# belt_output.net
KiCad netlist of a schematic drawn in Altium Designer
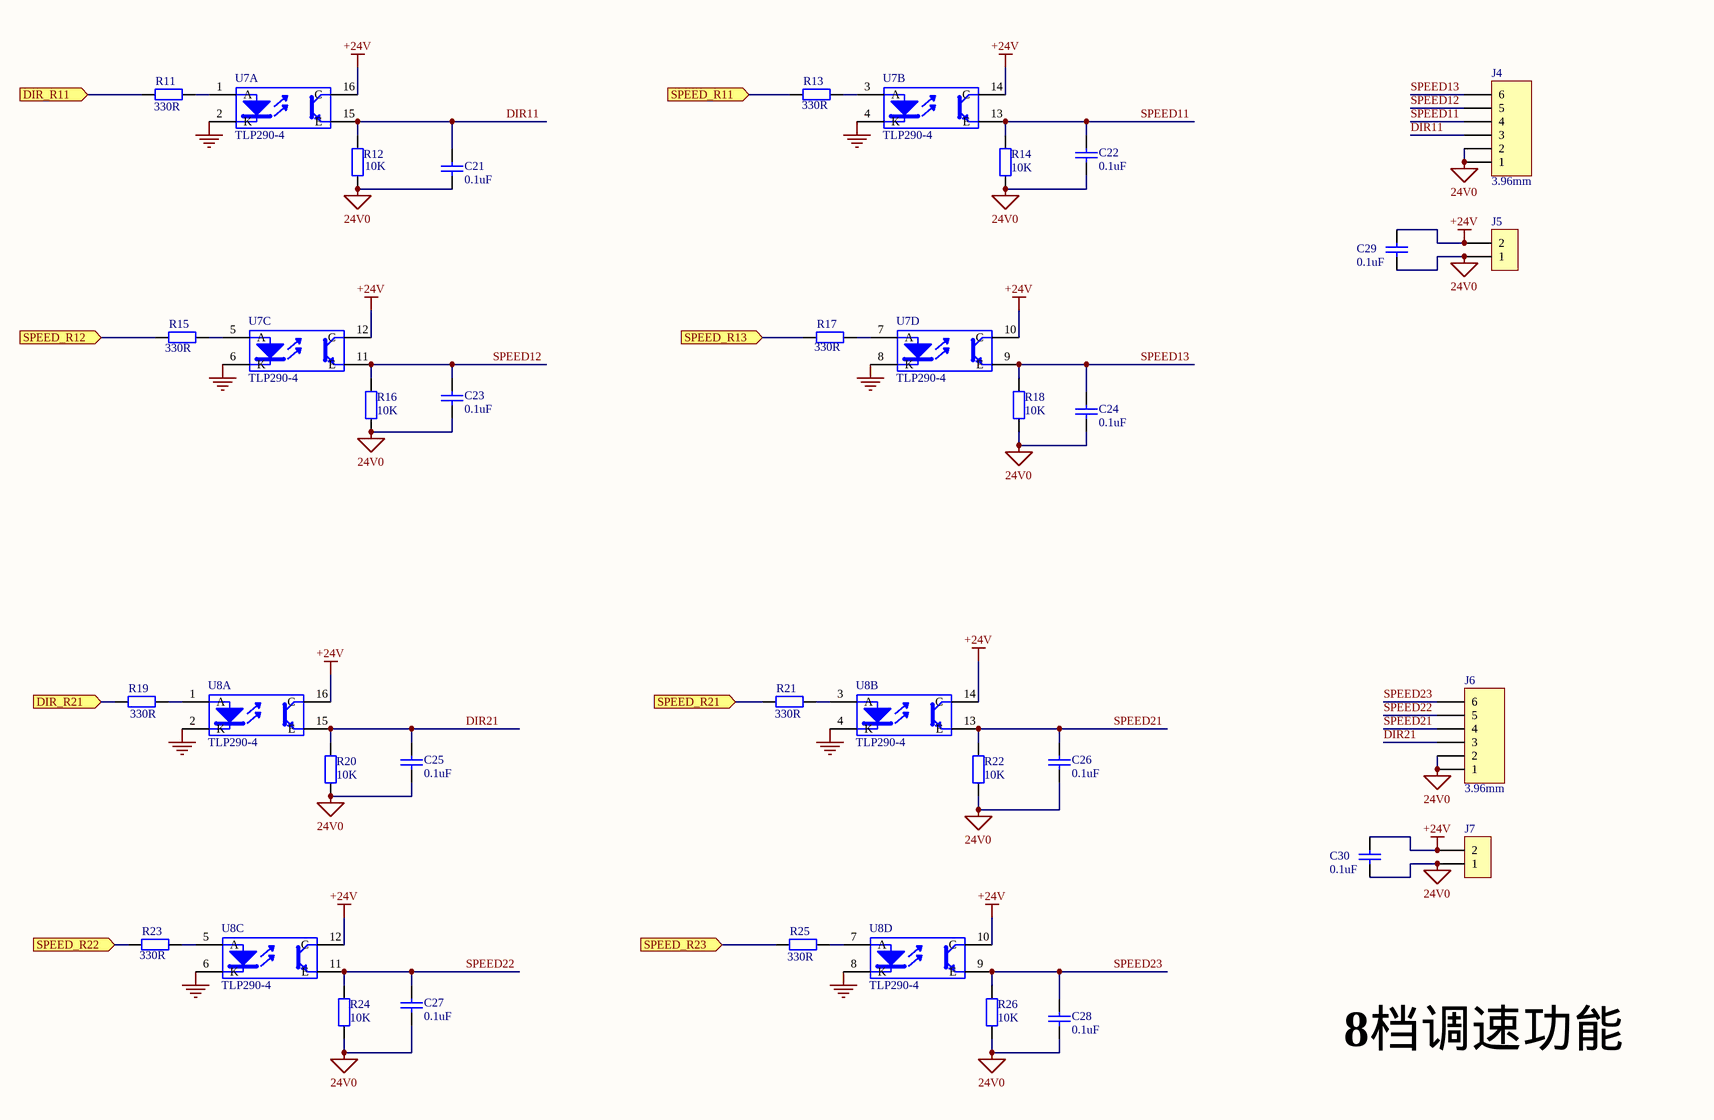
[diagram p0: belt_output.SchDoc]

(export (version "E")
  (design (tool "Eeschema 10.0.6"))
  (components
    (comp (ref "C21")
      (value "0.1uF")
      (footprint "0805_CAP")
      (description "Capacitor")
      (fields (field (name "PUBLISHER") "Altium Limited"))
      (libsource (lib "Miscellaneous Devices") (part "Cap"))
    )
    (comp (ref "C22")
      (value "0.1uF")
      (footprint "0805_CAP")
      (description "Capacitor")
      (fields (field (name "PUBLISHER") "Altium Limited"))
      (libsource (lib "Miscellaneous Devices") (part "Cap"))
    )
    (comp (ref "C23")
      (value "0.1uF")
      (footprint "0805_CAP")
      (description "Capacitor")
      (fields (field (name "PUBLISHER") "Altium Limited"))
      (libsource (lib "Miscellaneous Devices") (part "Cap"))
    )
    (comp (ref "C24")
      (value "0.1uF")
      (footprint "0805_CAP")
      (description "Capacitor")
      (fields (field (name "PUBLISHER") "Altium Limited"))
      (libsource (lib "Miscellaneous Devices") (part "Cap"))
    )
    (comp (ref "C25")
      (value "0.1uF")
      (footprint "0805_CAP")
      (description "Capacitor")
      (fields (field (name "PUBLISHER") "Altium Limited"))
      (libsource (lib "Miscellaneous Devices") (part "Cap"))
    )
    (comp (ref "C26")
      (value "0.1uF")
      (footprint "0805_CAP")
      (description "Capacitor")
      (fields (field (name "PUBLISHER") "Altium Limited"))
      (libsource (lib "Miscellaneous Devices") (part "Cap"))
    )
    (comp (ref "C27")
      (value "0.1uF")
      (footprint "0805_CAP")
      (description "Capacitor")
      (fields (field (name "PUBLISHER") "Altium Limited"))
      (libsource (lib "Miscellaneous Devices") (part "Cap"))
    )
    (comp (ref "C28")
      (value "0.1uF")
      (footprint "0805_CAP")
      (description "Capacitor")
      (fields (field (name "PUBLISHER") "Altium Limited"))
      (libsource (lib "Miscellaneous Devices") (part "Cap"))
    )
    (comp (ref "C29")
      (value "0.1uF")
      (footprint "0805_CAP")
      (description "Capacitor")
      (fields (field (name "PUBLISHER") "Altium Limited"))
      (libsource (lib "Miscellaneous Devices") (part "Cap"))
    )
    (comp (ref "C30")
      (value "0.1uF")
      (footprint "0805_CAP")
      (description "Capacitor")
      (fields (field (name "PUBLISHER") "Altium Limited"))
      (libsource (lib "Miscellaneous Devices") (part "Cap"))
    )
    (comp (ref "J4")
      (value "3.96mm")
      (footprint "VH3.96_6P")
      (description "Header, 6-Pin, Right Angle")
      (fields (field (name "PUBLISHER") "Altium Limited"))
      (libsource (lib "Miscellaneous Connectors") (part "Header 6H"))
    )
    (comp (ref "J5")
      (value "HEADER1X2")
      (footprint "VH3.96_2P")
      (libsource (lib "myIntegrated_Library1") (part "HEADER1X2"))
    )
    (comp (ref "J6")
      (value "3.96mm")
      (footprint "VH3.96_6P")
      (description "Header, 6-Pin")
      (fields (field (name "PUBLISHER") "Altium Limited"))
      (libsource (lib "Miscellaneous Connectors") (part "Header 6"))
    )
    (comp (ref "J7")
      (value "HEADER1X2")
      (footprint "VH3.96_2P")
      (libsource (lib "myIntegrated_Library1") (part "HEADER1X2"))
    )
    (comp (ref "R11")
      (value "330R")
      (footprint "0805_RES")
      (description "Resistor")
      (fields (field (name "PUBLISHER") "Altium Limited"))
      (libsource (lib "Miscellaneous Devices") (part "Res2"))
    )
    (comp (ref "R12")
      (value "10K")
      (footprint "0805_RES")
      (description "Resistor")
      (fields (field (name "PUBLISHER") "Altium Limited"))
      (libsource (lib "") (part "Res2_1"))
    )
    (comp (ref "R13")
      (value "330R")
      (footprint "0805_RES")
      (description "Resistor")
      (fields (field (name "PUBLISHER") "Altium Limited"))
      (libsource (lib "Miscellaneous Devices") (part "Res2"))
    )
    (comp (ref "R14")
      (value "10K")
      (footprint "0805_RES")
      (description "Resistor")
      (fields (field (name "PUBLISHER") "Altium Limited"))
      (libsource (lib "") (part "Res2_1"))
    )
    (comp (ref "R15")
      (value "330R")
      (footprint "0805_RES")
      (description "Resistor")
      (fields (field (name "PUBLISHER") "Altium Limited"))
      (libsource (lib "Miscellaneous Devices") (part "Res2"))
    )
    (comp (ref "R16")
      (value "10K")
      (footprint "0805_RES")
      (description "Resistor")
      (fields (field (name "PUBLISHER") "Altium Limited"))
      (libsource (lib "") (part "Res2_1"))
    )
    (comp (ref "R17")
      (value "330R")
      (footprint "0805_RES")
      (description "Resistor")
      (fields (field (name "PUBLISHER") "Altium Limited"))
      (libsource (lib "Miscellaneous Devices") (part "Res2"))
    )
    (comp (ref "R18")
      (value "10K")
      (footprint "0805_RES")
      (description "Resistor")
      (fields (field (name "PUBLISHER") "Altium Limited"))
      (libsource (lib "") (part "Res2_1"))
    )
    (comp (ref "R19")
      (value "330R")
      (footprint "0805_RES")
      (description "Resistor")
      (fields (field (name "PUBLISHER") "Altium Limited"))
      (libsource (lib "Miscellaneous Devices") (part "Res2"))
    )
    (comp (ref "R20")
      (value "10K")
      (footprint "0805_RES")
      (description "Resistor")
      (fields (field (name "PUBLISHER") "Altium Limited"))
      (libsource (lib "") (part "Res2_1"))
    )
    (comp (ref "R21")
      (value "330R")
      (footprint "0805_RES")
      (description "Resistor")
      (fields (field (name "PUBLISHER") "Altium Limited"))
      (libsource (lib "Miscellaneous Devices") (part "Res2"))
    )
    (comp (ref "R22")
      (value "10K")
      (footprint "0805_RES")
      (description "Resistor")
      (fields (field (name "PUBLISHER") "Altium Limited"))
      (libsource (lib "") (part "Res2_1"))
    )
    (comp (ref "R23")
      (value "330R")
      (footprint "0805_RES")
      (description "Resistor")
      (fields (field (name "PUBLISHER") "Altium Limited"))
      (libsource (lib "Miscellaneous Devices") (part "Res2"))
    )
    (comp (ref "R24")
      (value "10K")
      (footprint "0805_RES")
      (description "Resistor")
      (fields (field (name "PUBLISHER") "Altium Limited"))
      (libsource (lib "") (part "Res2_1"))
    )
    (comp (ref "R25")
      (value "330R")
      (footprint "0805_RES")
      (description "Resistor")
      (fields (field (name "PUBLISHER") "Altium Limited"))
      (libsource (lib "Miscellaneous Devices") (part "Res2"))
    )
    (comp (ref "R26")
      (value "10K")
      (footprint "0805_RES")
      (description "Resistor")
      (fields (field (name "PUBLISHER") "Altium Limited"))
      (libsource (lib "") (part "Res2_1"))
    )
    (comp (ref "U7") (value "TLP290-4") (footprint "SO16") (libsource (lib "WH V20") (part "TLP521-4")))
    (comp (ref "U8") (value "TLP290-4") (footprint "SO16") (libsource (lib "WH V20") (part "TLP521-4")))
  )
  (nets
    (net (code "1") (name "+24V") (class "Default")
      (node (ref "C29") (pin "1") (pinfunction "1_1") (pintype "passive"))
      (node (ref "C30") (pin "1") (pinfunction "1_1") (pintype "passive"))
      (node (ref "J5") (pin "2") (pinfunction "2_2") (pintype "passive"))
      (node (ref "J7") (pin "2") (pinfunction "2_2") (pintype "passive"))
      (node (ref "U7") (pin "10") (pinfunction "C_10") (pintype "passive"))
      (node (ref "U7") (pin "12") (pinfunction "C_12") (pintype "passive"))
      (node (ref "U7") (pin "14") (pinfunction "C_14") (pintype "passive"))
      (node (ref "U7") (pin "16") (pinfunction "C_16") (pintype "passive"))
      (node (ref "U8") (pin "10") (pinfunction "C_10") (pintype "passive"))
      (node (ref "U8") (pin "12") (pinfunction "C_12") (pintype "passive"))
      (node (ref "U8") (pin "14") (pinfunction "C_14") (pintype "passive"))
      (node (ref "U8") (pin "16") (pinfunction "C_16") (pintype "passive"))
    )
    (net (code "2") (name "/DIR11") (class "Default")
      (node (ref "C21") (pin "1") (pinfunction "1_1") (pintype "passive"))
      (node (ref "J4") (pin "3") (pinfunction "3_3") (pintype "passive"))
      (node (ref "R12") (pin "2") (pinfunction "2_2") (pintype "passive"))
      (node (ref "U7") (pin "15") (pinfunction "E_15") (pintype "passive"))
    )
    (net (code "3") (name "/DIR21") (class "Default")
      (node (ref "C25") (pin "1") (pinfunction "1_1") (pintype "passive"))
      (node (ref "J6") (pin "3") (pinfunction "3_3") (pintype "passive"))
      (node (ref "R20") (pin "2") (pinfunction "2_2") (pintype "passive"))
      (node (ref "U8") (pin "15") (pinfunction "E_15") (pintype "passive"))
    )
    (net (code "4") (name "/DIR_R11") (class "Default")
      (node (ref "R11") (pin "1") (pinfunction "1_1") (pintype "passive"))
    )
    (net (code "5") (name "/DIR_R21") (class "Default")
      (node (ref "R19") (pin "1") (pinfunction "1_1") (pintype "passive"))
    )
    (net (code "6") (name "/SPEED11") (class "Default")
      (node (ref "C22") (pin "1") (pinfunction "1_1") (pintype "passive"))
      (node (ref "J4") (pin "4") (pinfunction "4_4") (pintype "passive"))
      (node (ref "R14") (pin "2") (pinfunction "2_2") (pintype "passive"))
      (node (ref "U7") (pin "13") (pinfunction "E_13") (pintype "passive"))
    )
    (net (code "7") (name "/SPEED12") (class "Default")
      (node (ref "C23") (pin "1") (pinfunction "1_1") (pintype "passive"))
      (node (ref "J4") (pin "5") (pinfunction "5_5") (pintype "passive"))
      (node (ref "R16") (pin "2") (pinfunction "2_2") (pintype "passive"))
      (node (ref "U7") (pin "11") (pinfunction "E_11") (pintype "passive"))
    )
    (net (code "8") (name "/SPEED13") (class "Default")
      (node (ref "C24") (pin "1") (pinfunction "1_1") (pintype "passive"))
      (node (ref "J4") (pin "6") (pinfunction "6_6") (pintype "passive"))
      (node (ref "R18") (pin "2") (pinfunction "2_2") (pintype "passive"))
      (node (ref "U7") (pin "9") (pinfunction "E_9") (pintype "passive"))
    )
    (net (code "9") (name "/SPEED21") (class "Default")
      (node (ref "C26") (pin "1") (pinfunction "1_1") (pintype "passive"))
      (node (ref "J6") (pin "4") (pinfunction "4_4") (pintype "passive"))
      (node (ref "R22") (pin "2") (pinfunction "2_2") (pintype "passive"))
      (node (ref "U8") (pin "13") (pinfunction "E_13") (pintype "passive"))
    )
    (net (code "10") (name "/SPEED22") (class "Default")
      (node (ref "C27") (pin "1") (pinfunction "1_1") (pintype "passive"))
      (node (ref "J6") (pin "5") (pinfunction "5_5") (pintype "passive"))
      (node (ref "R24") (pin "2") (pinfunction "2_2") (pintype "passive"))
      (node (ref "U8") (pin "11") (pinfunction "E_11") (pintype "passive"))
    )
    (net (code "11") (name "/SPEED23") (class "Default")
      (node (ref "C28") (pin "1") (pinfunction "1_1") (pintype "passive"))
      (node (ref "J6") (pin "6") (pinfunction "6_6") (pintype "passive"))
      (node (ref "R26") (pin "2") (pinfunction "2_2") (pintype "passive"))
      (node (ref "U8") (pin "9") (pinfunction "E_9") (pintype "passive"))
    )
    (net (code "12") (name "/SPEED_R11") (class "Default")
      (node (ref "R13") (pin "1") (pinfunction "1_1") (pintype "passive"))
    )
    (net (code "13") (name "/SPEED_R12") (class "Default")
      (node (ref "R15") (pin "1") (pinfunction "1_1") (pintype "passive"))
    )
    (net (code "14") (name "/SPEED_R13") (class "Default")
      (node (ref "R17") (pin "1") (pinfunction "1_1") (pintype "passive"))
    )
    (net (code "15") (name "/SPEED_R21") (class "Default")
      (node (ref "R21") (pin "1") (pinfunction "1_1") (pintype "passive"))
    )
    (net (code "16") (name "/SPEED_R22") (class "Default")
      (node (ref "R23") (pin "1") (pinfunction "1_1") (pintype "passive"))
    )
    (net (code "17") (name "/SPEED_R23") (class "Default")
      (node (ref "R25") (pin "1") (pinfunction "1_1") (pintype "passive"))
    )
    (net (code "18") (name "24V0") (class "Default")
      (node (ref "C21") (pin "2") (pinfunction "2_2") (pintype "passive"))
      (node (ref "C22") (pin "2") (pinfunction "2_2") (pintype "passive"))
      (node (ref "C23") (pin "2") (pinfunction "2_2") (pintype "passive"))
      (node (ref "C24") (pin "2") (pinfunction "2_2") (pintype "passive"))
      (node (ref "C25") (pin "2") (pinfunction "2_2") (pintype "passive"))
      (node (ref "C26") (pin "2") (pinfunction "2_2") (pintype "passive"))
      (node (ref "C27") (pin "2") (pinfunction "2_2") (pintype "passive"))
      (node (ref "C28") (pin "2") (pinfunction "2_2") (pintype "passive"))
      (node (ref "C29") (pin "2") (pinfunction "2_2") (pintype "passive"))
      (node (ref "C30") (pin "2") (pinfunction "2_2") (pintype "passive"))
      (node (ref "J4") (pin "1") (pinfunction "1_1") (pintype "passive"))
      (node (ref "J4") (pin "2") (pinfunction "2_2") (pintype "passive"))
      (node (ref "J5") (pin "1") (pinfunction "1_1") (pintype "passive"))
      (node (ref "J6") (pin "1") (pinfunction "1_1") (pintype "passive"))
      (node (ref "J6") (pin "2") (pinfunction "2_2") (pintype "passive"))
      (node (ref "J7") (pin "1") (pinfunction "1_1") (pintype "passive"))
      (node (ref "R12") (pin "1") (pinfunction "1_1") (pintype "passive"))
      (node (ref "R14") (pin "1") (pinfunction "1_1") (pintype "passive"))
      (node (ref "R16") (pin "1") (pinfunction "1_1") (pintype "passive"))
      (node (ref "R18") (pin "1") (pinfunction "1_1") (pintype "passive"))
      (node (ref "R20") (pin "1") (pinfunction "1_1") (pintype "passive"))
      (node (ref "R22") (pin "1") (pinfunction "1_1") (pintype "passive"))
      (node (ref "R24") (pin "1") (pinfunction "1_1") (pintype "passive"))
      (node (ref "R26") (pin "1") (pinfunction "1_1") (pintype "passive"))
    )
    (net (code "19") (name "GND") (class "Default")
      (node (ref "U7") (pin "2") (pinfunction "K_2") (pintype "passive"))
      (node (ref "U7") (pin "4") (pinfunction "K_4") (pintype "passive"))
      (node (ref "U7") (pin "6") (pinfunction "K_6") (pintype "passive"))
      (node (ref "U7") (pin "8") (pinfunction "K_8") (pintype "passive"))
      (node (ref "U8") (pin "2") (pinfunction "K_2") (pintype "passive"))
      (node (ref "U8") (pin "4") (pinfunction "K_4") (pintype "passive"))
      (node (ref "U8") (pin "6") (pinfunction "K_6") (pintype "passive"))
      (node (ref "U8") (pin "8") (pinfunction "K_8") (pintype "passive"))
    )
    (net (code "20") (name "Net-(U7A-A)") (class "Default")
      (node (ref "R11") (pin "2") (pinfunction "2_2") (pintype "passive"))
      (node (ref "U7") (pin "1") (pinfunction "A_1") (pintype "passive"))
    )
    (net (code "21") (name "Net-(U7B-A)") (class "Default")
      (node (ref "R13") (pin "2") (pinfunction "2_2") (pintype "passive"))
      (node (ref "U7") (pin "3") (pinfunction "A_3") (pintype "passive"))
    )
    (net (code "22") (name "Net-(U7C-A)") (class "Default")
      (node (ref "R15") (pin "2") (pinfunction "2_2") (pintype "passive"))
      (node (ref "U7") (pin "5") (pinfunction "A_5") (pintype "passive"))
    )
    (net (code "23") (name "Net-(U7D-A)") (class "Default")
      (node (ref "R17") (pin "2") (pinfunction "2_2") (pintype "passive"))
      (node (ref "U7") (pin "7") (pinfunction "A_7") (pintype "passive"))
    )
    (net (code "24") (name "Net-(U8A-A)") (class "Default")
      (node (ref "R19") (pin "2") (pinfunction "2_2") (pintype "passive"))
      (node (ref "U8") (pin "1") (pinfunction "A_1") (pintype "passive"))
    )
    (net (code "25") (name "Net-(U8B-A)") (class "Default")
      (node (ref "R21") (pin "2") (pinfunction "2_2") (pintype "passive"))
      (node (ref "U8") (pin "3") (pinfunction "A_3") (pintype "passive"))
    )
    (net (code "26") (name "Net-(U8C-A)") (class "Default")
      (node (ref "R23") (pin "2") (pinfunction "2_2") (pintype "passive"))
      (node (ref "U8") (pin "5") (pinfunction "A_5") (pintype "passive"))
    )
    (net (code "27") (name "Net-(U8D-A)") (class "Default")
      (node (ref "R25") (pin "2") (pinfunction "2_2") (pintype "passive"))
      (node (ref "U8") (pin "7") (pinfunction "A_7") (pintype "passive"))
    )
  )
)
